# LCD.net
KiCad netlist of a schematic drawn in Altium Designer
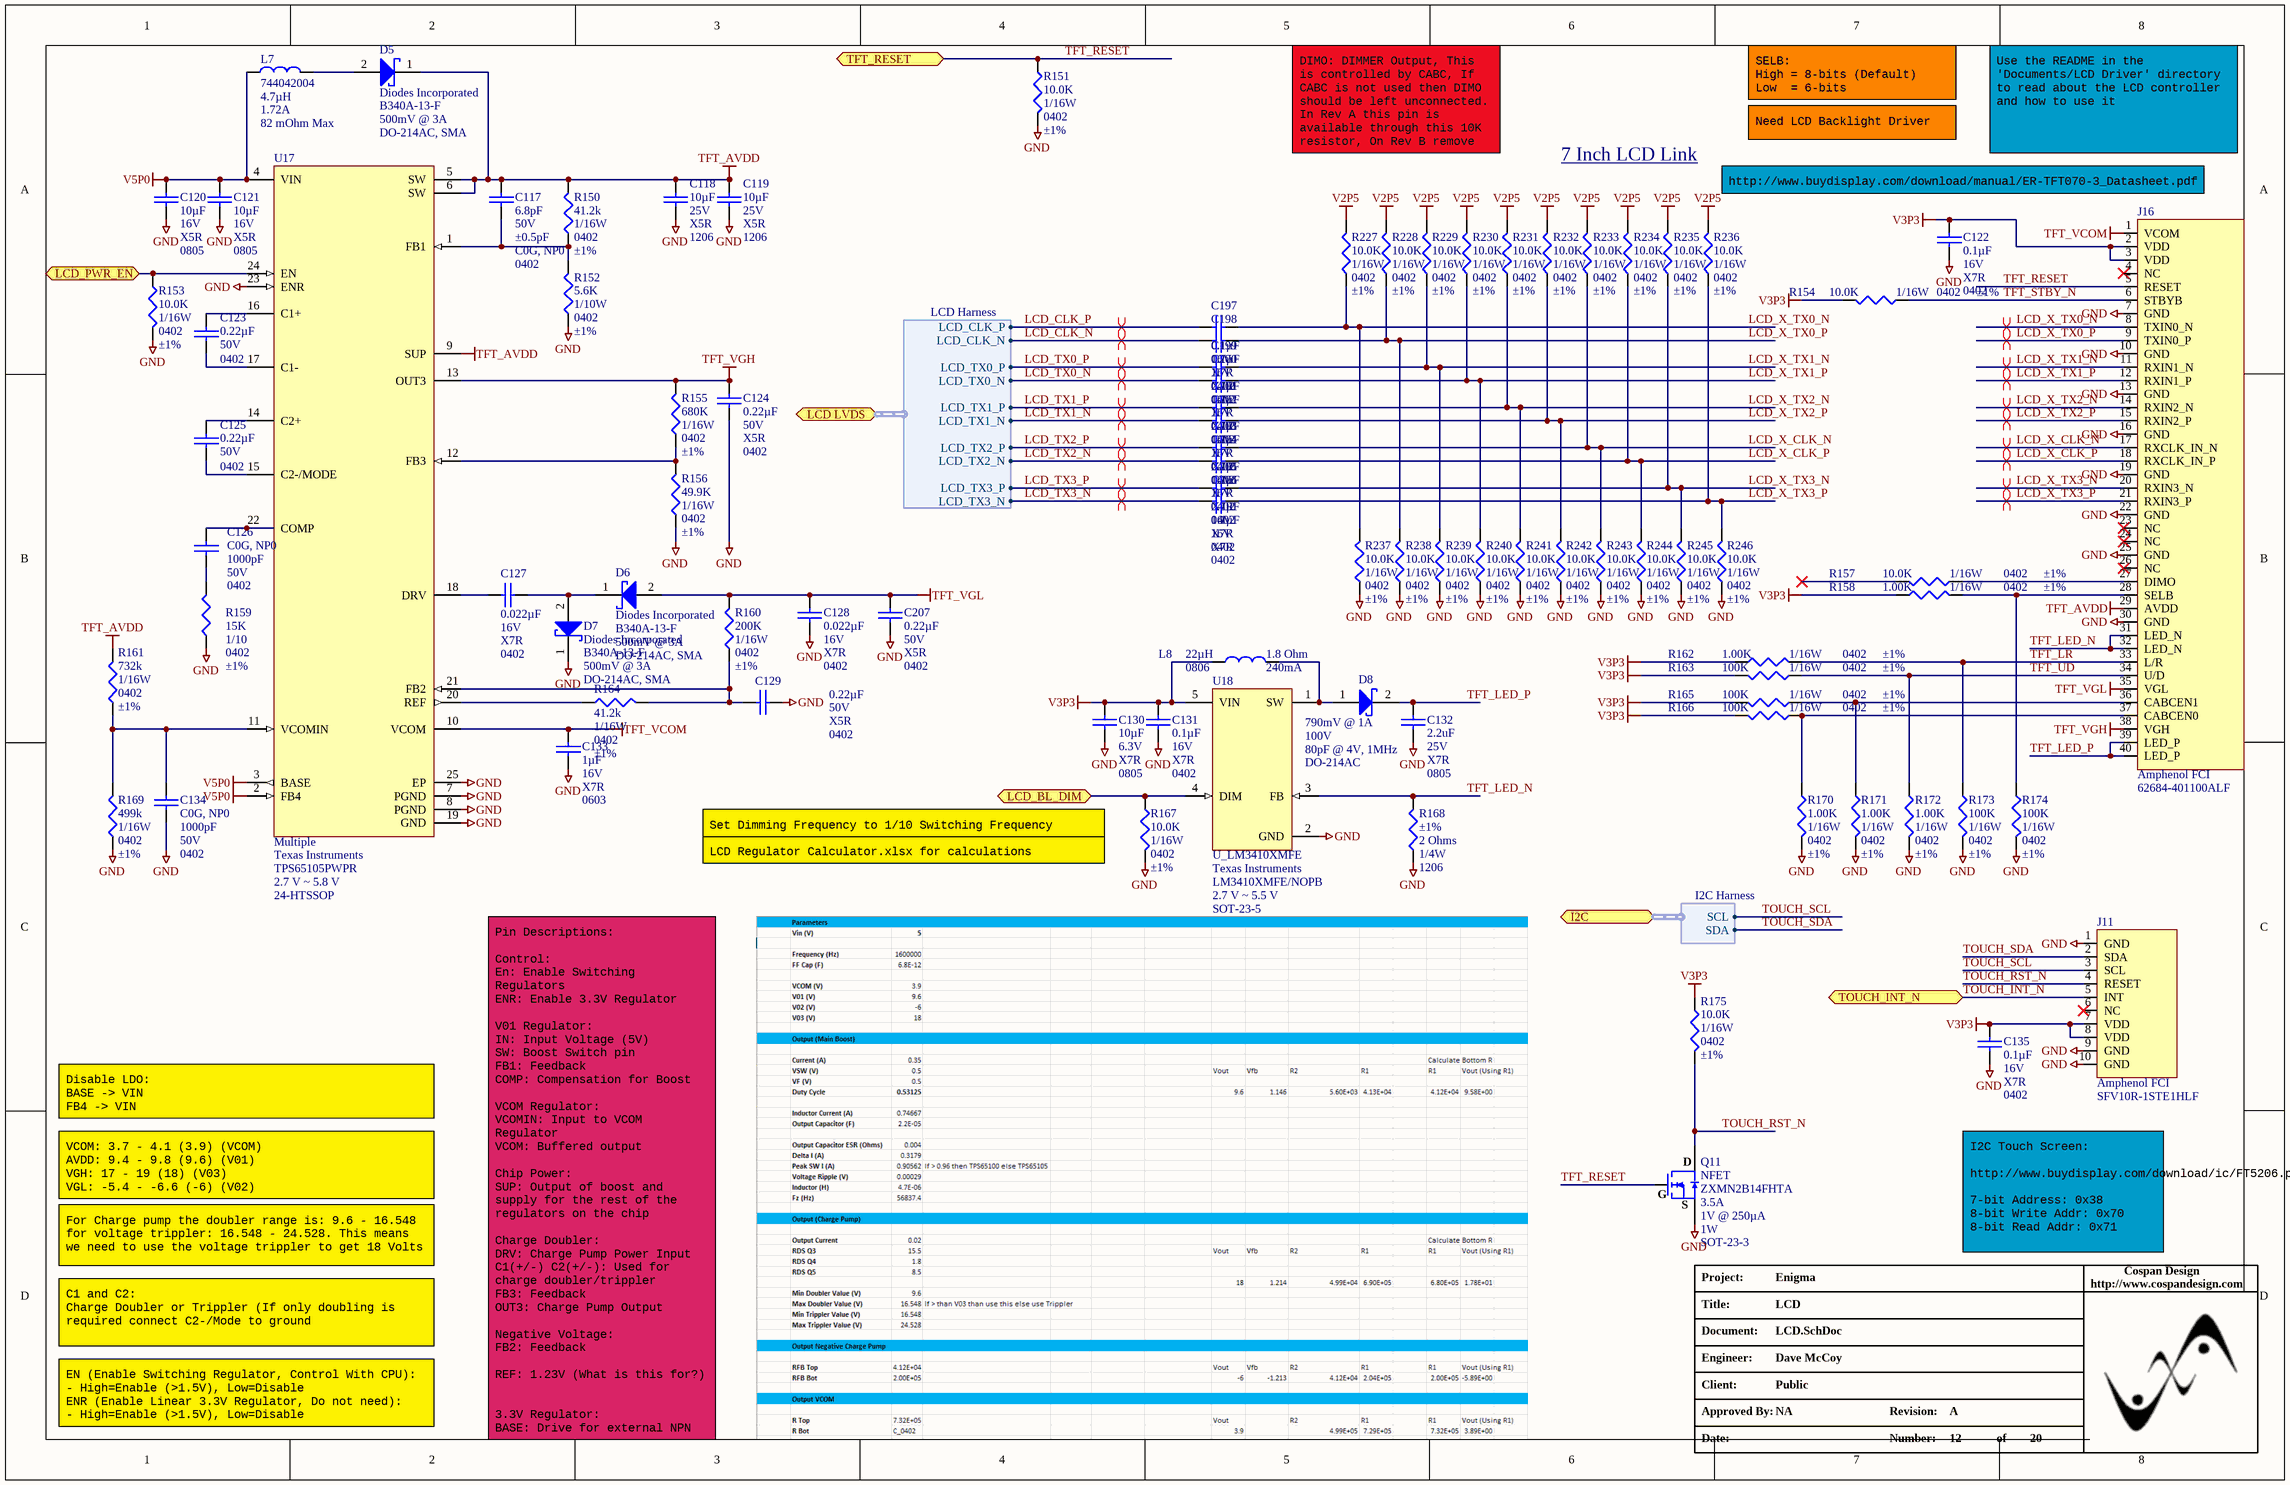
[diagram p0: LCD.SchDoc]

(export (version "E")
  (design (tool "Eeschema 10.0.6"))
  (components
    (comp (ref "C117")
      (value "6.8pF")
      (footprint "C_ERA-0402")
      (description "CAP CER 6.8PF 50V NP0 0402")
      (fields
        (field (name "MANUFACTURER") "Yageo")
        (field (name "MANUFACTURER PART NUMBER") "CC0402DRNPO9BN6R8")
        (field (name "CAPACITANCE") "6.8pF")
        (field (name "VOLTAGE - RATED") "50V")
        (field (name "TOLERANCE") "±0.5pF")
        (field (name "TEMPERATURE COEFFICIENT") "C0G, NP0")
        (field (name "PACKAGE / CASE") "0402")
      )
      (libsource (lib "Main LibraryX") (part "C_0402_6.8PF_50V"))
    )
    (comp (ref "C118")
      (value "10µF")
      (footprint "CAP-1206")
      (description "CAP CER 10UF 25V X5R 1206")
      (fields
        (field (name "MANUFACTURER") "Murata Electronics North America")
        (field (name "MANUFACTURER PART NUMBER") "GRM31CR61E106MA12L")
        (field (name "CAPACITANCE") "10µF")
        (field (name "VOLTAGE - RATED") "25V")
        (field (name "TEMPERATURE COEFFICIENT") "X5R")
        (field (name "PACKAGE / CASE") "1206")
      )
      (libsource (lib "Main Library") (part "C_1206_10UF_25V"))
    )
    (comp (ref "C119")
      (value "10µF")
      (footprint "CAP-1206")
      (description "CAP CER 10UF 25V X5R 1206")
      (fields
        (field (name "MANUFACTURER") "Murata Electronics North America")
        (field (name "MANUFACTURER PART NUMBER") "GRM31CR61E106MA12L")
        (field (name "CAPACITANCE") "10µF")
        (field (name "VOLTAGE - RATED") "25V")
        (field (name "TEMPERATURE COEFFICIENT") "X5R")
        (field (name "PACKAGE / CASE") "1206")
      )
      (libsource (lib "Main Library") (part "C_1206_10UF_25V"))
    )
    (comp (ref "C120")
      (value "10µF")
      (footprint "C_ERA-0805")
      (description "CAP CER 10uF 16V X5R 20% 0805")
      (fields
        (field (name "MANUFACTURER") "Taiyo Yuden")
        (field (name "MANUFACTURER PART NUMBER") "EMK212BJ106KG-T")
        (field (name "CAPACITANCE") "10µF")
        (field (name "VOLTAGE - RATED") "16V")
        (field (name "TEMPERATURE COEFFICIENT") "X5R")
        (field (name "PACKAGE / CASE") "0805")
      )
      (libsource (lib "Main LibraryX") (part "C_0805_10UF_16V"))
    )
    (comp (ref "C121")
      (value "10µF")
      (footprint "C_ERA-0805")
      (description "CAP CER 10uF 16V X5R 20% 0805")
      (fields
        (field (name "MANUFACTURER") "Taiyo Yuden")
        (field (name "MANUFACTURER PART NUMBER") "EMK212BJ106KG-T")
        (field (name "CAPACITANCE") "10µF")
        (field (name "VOLTAGE - RATED") "16V")
        (field (name "TEMPERATURE COEFFICIENT") "X5R")
        (field (name "PACKAGE / CASE") "0805")
      )
      (libsource (lib "Main LibraryX") (part "C_0805_10UF_16V"))
    )
    (comp (ref "C122")
      (value "0.1uF")
      (footprint "C_0402")
      (description "CAP CER .10UF 16V X7R 0402")
      (fields
        (field (name "MANUFACTURER") "Murata Electronics North America")
        (field (name "MANUFACTURER PART NUMBER") "GRM155R71C104KA88J")
        (field (name "CAPACITANCE") "0.1µF")
        (field (name "VOLTAGE - RATED") "16V")
        (field (name "TEMPERATURE COEFFICIENT") "X7R")
        (field (name "PACKAGE / CASE") "0402")
      )
      (libsource (lib "Main LibraryX") (part "C_0402_0.1UF_16V"))
    )
    (comp (ref "C123")
      (value "C_0402_0.22UF_50V")
      (footprint "C_ERA-0402")
      (description "CAP CER 0.22UF 50V X5R 0402")
      (fields
        (field (name "MANUFACTURER") "Taiyo Yuden")
        (field (name "MANUFACTURER PART NUMBER") "UMK105BJ224KV-F")
        (field (name "CAPACITANCE") "0.22µF")
        (field (name "VOLTAGE - RATED") "50V")
        (field (name "PACKAGE / CASE") "0402")
      )
      (libsource (lib "Main Library") (part "C_0402_0.22UF_50V"))
    )
    (comp (ref "C124")
      (value "C_0402_0.22UF_50V")
      (footprint "C_ERA-0402")
      (description "CAP CER 0.22UF 50V X5R 0402")
      (fields
        (field (name "MANUFACTURER") "Taiyo Yuden")
        (field (name "MANUFACTURER PART NUMBER") "UMK105BJ224KV-F")
        (field (name "CAPACITANCE") "0.22µF")
        (field (name "VOLTAGE - RATED") "50V")
        (field (name "TEMPERATURE COEFFICIENT") "X5R")
        (field (name "PACKAGE / CASE") "0402")
      )
      (libsource (lib "Main Library") (part "C_0402_0.22UF_50V"))
    )
    (comp (ref "C125")
      (value "C_0402_0.22UF_50V")
      (footprint "C_ERA-0402")
      (description "CAP CER 0.22UF 50V X5R 0402")
      (fields
        (field (name "MANUFACTURER") "Taiyo Yuden")
        (field (name "MANUFACTURER PART NUMBER") "UMK105BJ224KV-F")
        (field (name "CAPACITANCE") "0.22µF")
        (field (name "VOLTAGE - RATED") "50V")
        (field (name "PACKAGE / CASE") "0402")
      )
      (libsource (lib "Main Library") (part "C_0402_0.22UF_50V"))
    )
    (comp (ref "C126")
      (value "1000pF")
      (footprint "C_ERA-0402")
      (description "CAP CER 1000PF 50V C0G 0402")
      (fields
        (field (name "MANUFACTURER") "Murata Electronics North America")
        (field (name "MANUFACTURER PART NUMBER") "GRM1555C1H102JA01D")
        (field (name "TEMPERATURE COEFFICIENT") "C0G, NP0")
        (field (name "CAPACITANCE") "1000pF")
        (field (name "VOLTAGE - RATED") "50V")
        (field (name "PACKAGE / CASE") "0402")
      )
      (libsource (lib "Main Library") (part "C_0402_1000PF_50V"))
    )
    (comp (ref "C127")
      (value "0.022UF")
      (footprint "C_ERA-0402")
      (description "CAP CER 22000PF 16V X7R 0402")
      (fields
        (field (name "MANUFACTURER") "Murata Electronics North America")
        (field (name "MANUFACTURER PART NUMBER") "GRM155R71C223KA01D")
        (field (name "CAPACITANCE") "0.022µF")
        (field (name "VOLTAGE - RATED") "16V")
        (field (name "TEMPERATURE COEFFICIENT") "X7R")
        (field (name "PACKAGE / CASE") "0402")
      )
      (libsource (lib "Main Library") (part "C_0402_0.022UF"))
    )
    (comp (ref "C128")
      (value "0.022UF")
      (footprint "C_ERA-0402")
      (description "CAP CER 22000PF 16V X7R 0402")
      (fields
        (field (name "MANUFACTURER") "Murata Electronics North America")
        (field (name "MANUFACTURER PART NUMBER") "GRM155R71C223KA01D")
        (field (name "CAPACITANCE") "0.022µF")
        (field (name "VOLTAGE - RATED") "16V")
        (field (name "TEMPERATURE COEFFICIENT") "X7R")
        (field (name "PACKAGE / CASE") "0402")
      )
      (libsource (lib "Main Library") (part "C_0402_0.022UF"))
    )
    (comp (ref "C129")
      (value "C_0402_0.22UF_50V")
      (footprint "C_ERA-0402")
      (description "CAP CER 0.22UF 50V X5R 0402")
      (fields
        (field (name "MANUFACTURER") "Taiyo Yuden")
        (field (name "MANUFACTURER PART NUMBER") "UMK105BJ224KV-F")
        (field (name "CAPACITANCE") "0.22µF")
        (field (name "VOLTAGE - RATED") "50V")
        (field (name "TEMPERATURE COEFFICIENT") "X5R")
        (field (name "PACKAGE / CASE") "0402")
      )
      (libsource (lib "Main Library") (part "C_0402_0.22UF_50V"))
    )
    (comp (ref "C130")
      (value "10uF")
      (footprint "C_ERA-0805")
      (description "CAP CER 10UF 6.3V X7R 10% 0805")
      (fields
        (field (name "MANUFACTURER") "Taiyo Yuden")
        (field (name "MANUFACTURER PART NUMBER") "JMK212BJ106KD-T")
        (field (name "CAPACITANCE") "10µF")
        (field (name "VOLTAGE - RATED") "6.3V")
        (field (name "TEMPERATURE COEFFICIENT") "X7R")
        (field (name "PACKAGE / CASE") "0805")
      )
      (libsource (lib "Main LibraryX") (part "C_0805_10UF_6.3V"))
    )
    (comp (ref "C131")
      (value "0.1uF")
      (footprint "C_0402")
      (description "CAP CER .10UF 16V X7R 0402")
      (fields
        (field (name "MANUFACTURER") "Murata Electronics North America")
        (field (name "MANUFACTURER PART NUMBER") "GRM155R71C104KA88J")
        (field (name "CAPACITANCE") "0.1µF")
        (field (name "VOLTAGE - RATED") "16V")
        (field (name "TEMPERATURE COEFFICIENT") "X7R")
        (field (name "PACKAGE / CASE") "0402")
      )
      (libsource (lib "Main LibraryX") (part "C_0402_0.1UF_16V"))
    )
    (comp (ref "C132")
      (value "C_0805_2.2uF_25V")
      (footprint "C_ERA-0805")
      (fields
        (field (name "MANUFACTURER") "Taiyo Yuden")
        (field (name "MANUFACTURER PART NUMBER") "TMK212B7225KG-TR")
        (field (name "TOLERANCE") "±10%")
        (field (name "CAPACITANCE") "2.2uF")
        (field (name "VOLTAGE - RATED") "25V")
        (field (name "TEMPERATURE COEFFICIENT") "X7R")
        (field (name "PACKAGE / CASE") "0805")
      )
      (libsource (lib "Cospan Design") (part "C_0805_2.2uF_25V"))
    )
    (comp (ref "C133")
      (value "C_0603_1µF_16V")
      (footprint "C_ERA-0603")
      (description "CAP CER 1UF 16V X7R 0603")
      (fields
        (field (name "MANUFACTURER") "Yageo")
        (field (name "MANUFACTURER PART NUMBER") "CC0603KRX7R7BB105")
        (field (name "CAPACITANCE") "1µF")
        (field (name "VOLTAGE - RATED") "16V")
        (field (name "TEMPERATURE COEFFICIENT") "X7R")
        (field (name "PACKAGE / CASE") "0603")
      )
      (libsource (lib "Cospan Design") (part "C_0603_1µF_16V"))
    )
    (comp (ref "C134")
      (value "1000pF")
      (footprint "C_ERA-0402")
      (description "CAP CER 1000PF 50V C0G 0402")
      (fields
        (field (name "MANUFACTURER") "Murata Electronics North America")
        (field (name "MANUFACTURER PART NUMBER") "GRM1555C1H102JA01D")
        (field (name "TEMPERATURE COEFFICIENT") "C0G, NP0")
        (field (name "CAPACITANCE") "1000pF")
        (field (name "VOLTAGE - RATED") "50V")
        (field (name "PACKAGE / CASE") "0402")
      )
      (libsource (lib "Main Library") (part "C_0402_1000PF_50V"))
    )
    (comp (ref "C135")
      (value "0.1uF")
      (footprint "C_0402")
      (description "CAP CER .10UF 16V X7R 0402")
      (fields
        (field (name "MANUFACTURER") "Murata Electronics North America")
        (field (name "MANUFACTURER PART NUMBER") "GRM155R71C104KA88J")
        (field (name "CAPACITANCE") "0.1µF")
        (field (name "VOLTAGE - RATED") "16V")
        (field (name "TEMPERATURE COEFFICIENT") "X7R")
        (field (name "PACKAGE / CASE") "0402")
      )
      (libsource (lib "Main LibraryX") (part "C_0402_0.1UF_16V"))
    )
    (comp (ref "C197")
      (value "0.1uF")
      (footprint "C_0402")
      (description "CAP CER .10UF 16V X7R 0402")
      (fields
        (field (name "MANUFACTURER") "Murata Electronics North America")
        (field (name "MANUFACTURER PART NUMBER") "GRM155R71C104KA88J")
        (field (name "CAPACITANCE") "0.1µF")
        (field (name "VOLTAGE - RATED") "16V")
        (field (name "TEMPERATURE COEFFICIENT") "X7R")
        (field (name "PACKAGE / CASE") "0402")
      )
      (libsource (lib "Main LibraryX") (part "C_0402_0.1UF_16V"))
    )
    (comp (ref "C198")
      (value "0.1uF")
      (footprint "C_0402")
      (description "CAP CER .10UF 16V X7R 0402")
      (fields
        (field (name "MANUFACTURER") "Murata Electronics North America")
        (field (name "MANUFACTURER PART NUMBER") "GRM155R71C104KA88J")
        (field (name "CAPACITANCE") "0.1µF")
        (field (name "VOLTAGE - RATED") "16V")
        (field (name "TEMPERATURE COEFFICIENT") "X7R")
        (field (name "PACKAGE / CASE") "0402")
      )
      (libsource (lib "Main LibraryX") (part "C_0402_0.1UF_16V"))
    )
    (comp (ref "C199")
      (value "0.1uF")
      (footprint "C_0402")
      (description "CAP CER .10UF 16V X7R 0402")
      (fields
        (field (name "MANUFACTURER") "Murata Electronics North America")
        (field (name "MANUFACTURER PART NUMBER") "GRM155R71C104KA88J")
        (field (name "CAPACITANCE") "0.1µF")
        (field (name "VOLTAGE - RATED") "16V")
        (field (name "TEMPERATURE COEFFICIENT") "X7R")
        (field (name "PACKAGE / CASE") "0402")
      )
      (libsource (lib "Main LibraryX") (part "C_0402_0.1UF_16V"))
    )
    (comp (ref "C200")
      (value "0.1uF")
      (footprint "C_0402")
      (description "CAP CER .10UF 16V X7R 0402")
      (fields
        (field (name "MANUFACTURER") "Murata Electronics North America")
        (field (name "MANUFACTURER PART NUMBER") "GRM155R71C104KA88J")
        (field (name "CAPACITANCE") "0.1µF")
        (field (name "VOLTAGE - RATED") "16V")
        (field (name "TEMPERATURE COEFFICIENT") "X7R")
        (field (name "PACKAGE / CASE") "0402")
      )
      (libsource (lib "Main LibraryX") (part "C_0402_0.1UF_16V"))
    )
    (comp (ref "C201")
      (value "0.1uF")
      (footprint "C_0402")
      (description "CAP CER .10UF 16V X7R 0402")
      (fields
        (field (name "MANUFACTURER") "Murata Electronics North America")
        (field (name "MANUFACTURER PART NUMBER") "GRM155R71C104KA88J")
        (field (name "CAPACITANCE") "0.1µF")
        (field (name "VOLTAGE - RATED") "16V")
        (field (name "TEMPERATURE COEFFICIENT") "X7R")
        (field (name "PACKAGE / CASE") "0402")
      )
      (libsource (lib "Main LibraryX") (part "C_0402_0.1UF_16V"))
    )
    (comp (ref "C202")
      (value "0.1uF")
      (footprint "C_0402")
      (description "CAP CER .10UF 16V X7R 0402")
      (fields
        (field (name "MANUFACTURER") "Murata Electronics North America")
        (field (name "MANUFACTURER PART NUMBER") "GRM155R71C104KA88J")
        (field (name "CAPACITANCE") "0.1µF")
        (field (name "VOLTAGE - RATED") "16V")
        (field (name "TEMPERATURE COEFFICIENT") "X7R")
        (field (name "PACKAGE / CASE") "0402")
      )
      (libsource (lib "Main LibraryX") (part "C_0402_0.1UF_16V"))
    )
    (comp (ref "C203")
      (value "0.1uF")
      (footprint "C_0402")
      (description "CAP CER .10UF 16V X7R 0402")
      (fields
        (field (name "MANUFACTURER") "Murata Electronics North America")
        (field (name "MANUFACTURER PART NUMBER") "GRM155R71C104KA88J")
        (field (name "CAPACITANCE") "0.1µF")
        (field (name "VOLTAGE - RATED") "16V")
        (field (name "TEMPERATURE COEFFICIENT") "X7R")
        (field (name "PACKAGE / CASE") "0402")
      )
      (libsource (lib "Main LibraryX") (part "C_0402_0.1UF_16V"))
    )
    (comp (ref "C204")
      (value "0.1uF")
      (footprint "C_0402")
      (description "CAP CER .10UF 16V X7R 0402")
      (fields
        (field (name "MANUFACTURER") "Murata Electronics North America")
        (field (name "MANUFACTURER PART NUMBER") "GRM155R71C104KA88J")
        (field (name "CAPACITANCE") "0.1µF")
        (field (name "VOLTAGE - RATED") "16V")
        (field (name "TEMPERATURE COEFFICIENT") "X7R")
        (field (name "PACKAGE / CASE") "0402")
      )
      (libsource (lib "Main LibraryX") (part "C_0402_0.1UF_16V"))
    )
    (comp (ref "C205")
      (value "0.1uF")
      (footprint "C_0402")
      (description "CAP CER .10UF 16V X7R 0402")
      (fields
        (field (name "MANUFACTURER") "Murata Electronics North America")
        (field (name "MANUFACTURER PART NUMBER") "GRM155R71C104KA88J")
        (field (name "CAPACITANCE") "0.1µF")
        (field (name "VOLTAGE - RATED") "16V")
        (field (name "TEMPERATURE COEFFICIENT") "X7R")
        (field (name "PACKAGE / CASE") "0402")
      )
      (libsource (lib "Main LibraryX") (part "C_0402_0.1UF_16V"))
    )
    (comp (ref "C206")
      (value "0.1uF")
      (footprint "C_0402")
      (description "CAP CER .10UF 16V X7R 0402")
      (fields
        (field (name "MANUFACTURER") "Murata Electronics North America")
        (field (name "MANUFACTURER PART NUMBER") "GRM155R71C104KA88J")
        (field (name "CAPACITANCE") "0.1µF")
        (field (name "VOLTAGE - RATED") "16V")
        (field (name "TEMPERATURE COEFFICIENT") "X7R")
        (field (name "PACKAGE / CASE") "0402")
      )
      (libsource (lib "Main LibraryX") (part "C_0402_0.1UF_16V"))
    )
    (comp (ref "C207")
      (value "C_0402_0.22UF_50V")
      (footprint "C_ERA-0402")
      (description "CAP CER 0.22UF 50V X5R 0402")
      (fields
        (field (name "MANUFACTURER") "Taiyo Yuden")
        (field (name "MANUFACTURER PART NUMBER") "UMK105BJ224KV-F")
        (field (name "CAPACITANCE") "0.22µF")
        (field (name "VOLTAGE - RATED") "50V")
        (field (name "TEMPERATURE COEFFICIENT") "X5R")
        (field (name "PACKAGE / CASE") "0402")
      )
      (libsource (lib "Main Library") (part "C_0402_0.22UF_50V"))
    )
    (comp (ref "D5")
      (value "D_B340A-13-F")
      (footprint "SMA")
      (description "DIODE SCHOTTKY 40V 3A SMA")
      (fields
        (field (name "MANUFACTURER") "Diodes Incorporated")
        (field (name "MANUFACTURER PART NUMBER") "B340A-13-F")
        (field (name "VOLTAGE - FORWARD (VF) (MAX) @ IF") "500mV @ 3A")
        (field (name "PACKAGE / CASE") "DO-214AC, SMA")
      )
      (libsource (lib "Cospan Design") (part "D_B340A-13-F"))
    )
    (comp (ref "D6")
      (value "D_B340A-13-F")
      (footprint "SMA")
      (description "DIODE SCHOTTKY 40V 3A SMA")
      (fields
        (field (name "MANUFACTURER") "Diodes Incorporated")
        (field (name "MANUFACTURER PART NUMBER") "B340A-13-F")
        (field (name "VOLTAGE - FORWARD (VF) (MAX) @ IF") "500mV @ 3A")
        (field (name "PACKAGE / CASE") "DO-214AC, SMA")
      )
      (libsource (lib "Cospan Design") (part "D_B340A-13-F"))
    )
    (comp (ref "D7")
      (value "D_B340A-13-F")
      (footprint "SMA")
      (description "DIODE SCHOTTKY 40V 3A SMA")
      (fields
        (field (name "MANUFACTURER") "Diodes Incorporated")
        (field (name "MANUFACTURER PART NUMBER") "B340A-13-F")
        (field (name "VOLTAGE - FORWARD (VF) (MAX) @ IF") "500mV @ 3A")
        (field (name "PACKAGE / CASE") "DO-214AC, SMA")
      )
      (libsource (lib "Cospan Design") (part "D_B340A-13-F"))
    )
    (comp (ref "D8")
      (value "B1100-13-F")
      (footprint "DIOM5226X23L")
      (description "DIODE SCHOTTKY 100V 1A SMA")
      (fields
        (field (name "MANUFACTURER") "Diodes Inc")
        (field (name "VOLTAGE - FORWARD (VF) (MAX) @ IF") "790mV @ 1A")
        (field (name "VOLTAGE - DC REVERSE (VR) (MAX)") "100V")
        (field (name "CAPACITANCE @ VR, F") "80pF @ 4V, 1MHz")
        (field (name "PACKAGE / CASE") "DO-214AC")
      )
      (libsource (lib "Main Library") (part "D_SCHOTT_B1100-13-F"))
    )
    (comp (ref "J11")
      (value "J_FFC_CONN_RA_10PIN")
      (footprint "ER-CON10HT-1_BTM")
      (description "CONN FFC BOTTOM 10POS 0.50MM R/A")
      (fields
        (field (name "MANUFACTURER") "Amphenol FCI")
        (field (name "MANUFACTURER PART NUMBER") "SFV10R-1STE1HLF")
      )
      (libsource (lib "Cospan Design") (part "J_FFC_CONN_RA_10PIN"))
    )
    (comp (ref "J16")
      (value "J_FFC_CONN_RA_40PIN")
      (footprint "ER-CON40HT-1_BTM")
      (description "CONN FPC BOTTOM 40POS 0.50MM R/A")
      (fields
        (field (name "MANUFACTURER") "Amphenol FCI")
        (field (name "MANUFACTURER PART NUMBER") "62684-401100ALF")
      )
      (libsource (lib "Cospan Design") (part "J_FFC_CONN_RA_40PIN"))
    )
    (comp (ref "L7")
      (value "4.7uH")
      (footprint "INDP744042006")
      (description "INDUCTOR POWER 4.7UH 1.72A SMD")
      (fields
        (field (name "MANUFACTURER") "Wurth Electronics Inc")
        (field (name "TOLERANCE") "±30%")
        (field (name "MANUFACTURER PART NUMBER") "744042004")
        (field (name "INDUCTANCE") "4.7µH")
        (field (name "CURRENT") "1.72A")
        (field (name "DC RESISTANCE (DCR)") "82 mOhm Max")
      )
      (libsource (lib "Main Library") (part "L_4.70UH_1.72A_SMD"))
    )
    (comp (ref "L8")
      (value "CBC2016T220K")
      (footprint "L_0806")
      (description "INDUCTOR 22UH 10% 0806 SMD")
      (fields
        (field (name "MANUFACTURER") "Taiyo Yuden")
        (field (name "TOLERANCE") "±10%")
        (field (name "CURRENT") "240mA")
        (field (name "PACKAGE / CASE") "0806")
        (field (name "INDUCTANCE") "22µH")
        (field (name "DC RESISTANCE (DCR)") "1.8 Ohm")
      )
      (libsource (lib "Main Library") (part "L_0806_22uH"))
    )
    (comp (ref "Q11")
      (value "NFET")
      (footprint "SOT-23A")
      (description "MOSFET N-CH 20V 3.5A SOT23-3")
      (fields
        (field (name "MANUFACTURER") "Diodes Incorporated")
        (field (name "MANUFACTURER PART NUMBER") "ZXMN2B14FHTA")
        (field (name "CURRENT - CONTINUOUS DRAIN (ID) @ 25° C") "3.5A")
        (field (name "VGS(TH) (MAX) @ ID") "1V @ 250µA")
        (field (name "POWER - MAX") "1W")
        (field (name "PACKAGE / CASE") "SOT-23-3")
      )
      (libsource (lib "Main Library") (part "Q_NFET_3.50A_SOT23"))
    )
    (comp (ref "R150")
      (value "R_0402_41.2K")
      (footprint "R_0402")
      (description "RES SMD 41.2K OHM 1% 1/16W 0402")
      (fields
        (field (name "RESISTANCE IN OHMS") "41.2k")
        (field (name "POWER (WATTS)") "1/16W")
        (field (name "CASE") "0402")
        (field (name "TOLERANCE") "±1%")
        (field (name "MANUFACTURER") "Yageo")
        (field (name "MANUFACTURER PART NUMBER") "RC0402FR-0741K2L")
      )
      (libsource (lib "Cospan Design") (part "R_0402_41.2K"))
    )
    (comp (ref "R151")
      (value "R_0402_10.0K")
      (footprint "R_0402")
      (description "RES 10.0K OHM 1/16W 1% 0402 SMD")
      (fields
        (field (name "MANUFACTURER") "Stackpole Electronics Inc")
        (field (name "MANUFACTURER PART NUMBER") "RMCF0402FT10K0")
        (field (name "RESISTANCE IN OHMS") "10.0K")
        (field (name "POWER (WATTS)") "1/16W")
        (field (name "CASE") "0402")
        (field (name "TOLERANCE") "±1%")
      )
      (libsource (lib "Cospan Design") (part "R_0402_10.0K"))
    )
    (comp (ref "R152")
      (value "5.6k Ohms")
      (footprint "R_0402")
      (description "RES 5.60K OHM 1/10W 1% 0402 SMD")
      (fields
        (field (name "MANUFACTURER") "Yageo")
        (field (name "MANUFACTURER PART NUMBER") "RC0402FR-075K6L")
        (field (name "RESISTANCE IN OHMS") "5.6K")
        (field (name "POWER (WATTS)") "1/10W")
        (field (name "CASE") "0402")
        (field (name "TOLERANCE") "±1%")
      )
      (libsource (lib "Main LibraryX") (part "R_0402_5.6K"))
    )
    (comp (ref "R153")
      (value "R_0402_10.0K")
      (footprint "R_0402")
      (description "RES 10.0K OHM 1/16W 1% 0402 SMD")
      (fields
        (field (name "MANUFACTURER") "Stackpole Electronics Inc")
        (field (name "MANUFACTURER PART NUMBER") "RMCF0402FT10K0")
        (field (name "RESISTANCE IN OHMS") "10.0K")
        (field (name "POWER (WATTS)") "1/16W")
        (field (name "CASE") "0402")
        (field (name "TOLERANCE") "±1%")
      )
      (libsource (lib "Cospan Design") (part "R_0402_10.0K"))
    )
    (comp (ref "R154")
      (value "R_0402_10.0K")
      (footprint "R_0402")
      (description "RES 10.0K OHM 1/16W 1% 0402 SMD")
      (fields
        (field (name "MANUFACTURER") "Stackpole Electronics Inc")
        (field (name "MANUFACTURER PART NUMBER") "RMCF0402FT10K0")
        (field (name "RESISTANCE IN OHMS") "10.0K")
        (field (name "POWER (WATTS)") "1/16W")
        (field (name "CASE") "0402")
        (field (name "TOLERANCE") "±1%")
      )
      (libsource (lib "Cospan Design") (part "R_0402_10.0K"))
    )
    (comp (ref "R155")
      (value "R_0402_680K")
      (footprint "R_0402")
      (description "Res Thick Film 0402 68K Ohm 1% 0.1W(1/10W) Â±100ppm/Â°C Molded SMD Automotive Punched T/R")
      (fields
        (field (name "MANUFACTURER") "Yageo")
        (field (name "MANUFACTURER PART NUMBER") "RC0402FR-07680KL")
        (field (name "RESISTANCE IN OHMS") "680K")
        (field (name "POWER (WATTS)") "1/16W")
        (field (name "CASE") "0402")
        (field (name "TOLERANCE") "±1%")
      )
      (libsource (lib "Cospan Design") (part "R_0402_680K"))
    )
    (comp (ref "R156")
      (value "R_0402_49.9K")
      (footprint "R_0402")
      (description "RES 49.9K OHM 1/16W 1% 0402 SMD")
      (fields
        (field (name "MANUFACTURER") "Vishay Dale")
        (field (name "MANUFACTURER PART NUMBER") "CRCW040249K9FKED")
        (field (name "RESISTANCE IN OHMS") "49.9K")
        (field (name "POWER (WATTS)") "1/16W")
        (field (name "CASE") "0402")
        (field (name "TOLERANCE") "±1%")
      )
      (libsource (lib "Main LibraryX") (part "R_0402_49.9K"))
    )
    (comp (ref "R157")
      (value "R_0402_10.0K")
      (footprint "R_0402")
      (description "RES 10.0K OHM 1/16W 1% 0402 SMD")
      (fields
        (field (name "MANUFACTURER") "Stackpole Electronics Inc")
        (field (name "MANUFACTURER PART NUMBER") "RMCF0402FT10K0")
        (field (name "RESISTANCE IN OHMS") "10.0K")
        (field (name "POWER (WATTS)") "1/16W")
        (field (name "CASE") "0402")
        (field (name "TOLERANCE") "±1%")
      )
      (libsource (lib "Cospan Design") (part "R_0402_10.0K"))
    )
    (comp (ref "R158")
      (value "1.0k Ohms")
      (footprint "R_0402")
      (description "RES 1.00K OHM 1/16W 1% 0402 SMD")
      (fields
        (field (name "MANUFACTURER") "Yageo")
        (field (name "MANUFACTURER PART NUMBER") "RC0402FR-071KL")
        (field (name "RESISTANCE IN OHMS") "1.00K")
        (field (name "POWER (WATTS)") "1/16W")
        (field (name "CASE") "0402")
        (field (name "TOLERANCE") "±1%")
      )
      (libsource (lib "Cospan Design") (part "R_0402_1.0K"))
    )
    (comp (ref "R159")
      (value "R_0402_15.0K")
      (footprint "R_0402")
      (description "RES 15.0K OHM 1/10W 1% 0402 SMD")
      (fields
        (field (name "MANUFACTURER") "Panasonic - ECG")
        (field (name "MANUFACTURER PART NUMBER") "ERJ-2RKF1502X")
        (field (name "RESISTANCE IN OHMS") "15K")
        (field (name "POWER (WATTS)") "1/10")
        (field (name "CASE") "0402")
        (field (name "TOLERANCE") "±1%")
      )
      (libsource (lib "Main Library") (part "R_0402_15.0K"))
    )
    (comp (ref "R160")
      (value "R_0402_200.0K")
      (footprint "R_0402")
      (description "RES 200K OHM 1/16W 1% 0402 SMD")
      (fields
        (field (name "MANUFACTURER") "Yageo")
        (field (name "MANUFACTURER PART NUMBER") "RC0402FR-07200KL")
        (field (name "RESISTANCE IN OHMS") "200K")
        (field (name "POWER (WATTS)") "1/16W")
        (field (name "CASE") "0402")
        (field (name "TOLERANCE") "±1%")
      )
      (libsource (lib "Main Library") (part "R_0402_200.0K"))
    )
    (comp (ref "R161")
      (value "R_0402_732k")
      (footprint "R_0402")
      (description "RES SMD 732K OHM 1% 1/16W 0402")
      (fields
        (field (name "MANUFACTURER") "Yageo")
        (field (name "MANUFACTURER PART NUMBER") "RC0402FR-07732KL")
        (field (name "RESISTANCE IN OHMS") "732k")
        (field (name "POWER (WATTS)") "1/16W")
        (field (name "CASE") "0402")
        (field (name "TOLERANCE") "±1%")
      )
      (libsource (lib "Cospan Design") (part "R_0402_732k"))
    )
    (comp (ref "R162")
      (value "1.0k Ohms")
      (footprint "R_0402")
      (description "RES 1.00K OHM 1/16W 1% 0402 SMD")
      (fields
        (field (name "MANUFACTURER") "Yageo")
        (field (name "MANUFACTURER PART NUMBER") "RC0402FR-071KL")
        (field (name "RESISTANCE IN OHMS") "1.00K")
        (field (name "POWER (WATTS)") "1/16W")
        (field (name "CASE") "0402")
        (field (name "TOLERANCE") "±1%")
      )
      (libsource (lib "Cospan Design") (part "R_0402_1.0K"))
    )
    (comp (ref "R163")
      (value "R_0402_100K")
      (footprint "R_0402")
      (description "RES SMD 100K OHM 1% 1/16W 0402")
      (fields
        (field (name "MANUFACTURER") "Yageo")
        (field (name "MANUFACTURER PART NUMBER") "RC0402FR-07100KL")
        (field (name "RESISTANCE IN OHMS") "100K")
        (field (name "POWER (WATTS)") "1/16W")
        (field (name "CASE") "0402")
        (field (name "TOLERANCE") "±1%")
      )
      (libsource (lib "Cospan Design") (part "R_0402_100K"))
    )
    (comp (ref "R164")
      (value "R_0402_41.2K")
      (footprint "R_0402")
      (description "RES SMD 41.2K OHM 1% 1/16W 0402")
      (fields
        (field (name "RESISTANCE IN OHMS") "41.2k")
        (field (name "POWER (WATTS)") "1/16W")
        (field (name "CASE") "0402")
        (field (name "TOLERANCE") "±1%")
        (field (name "MANUFACTURER") "Yageo")
        (field (name "MANUFACTURER PART NUMBER") "RC0402FR-0741K2L")
      )
      (libsource (lib "Cospan Design") (part "R_0402_41.2K"))
    )
    (comp (ref "R165")
      (value "R_0402_100K")
      (footprint "R_0402")
      (description "RES SMD 100K OHM 1% 1/16W 0402")
      (fields
        (field (name "MANUFACTURER") "Yageo")
        (field (name "MANUFACTURER PART NUMBER") "RC0402FR-07100KL")
        (field (name "RESISTANCE IN OHMS") "100K")
        (field (name "POWER (WATTS)") "1/16W")
        (field (name "CASE") "0402")
        (field (name "TOLERANCE") "±1%")
      )
      (libsource (lib "Cospan Design") (part "R_0402_100K"))
    )
    (comp (ref "R166")
      (value "R_0402_100K")
      (footprint "R_0402")
      (description "RES SMD 100K OHM 1% 1/16W 0402")
      (fields
        (field (name "MANUFACTURER") "Yageo")
        (field (name "MANUFACTURER PART NUMBER") "RC0402FR-07100KL")
        (field (name "RESISTANCE IN OHMS") "100K")
        (field (name "POWER (WATTS)") "1/16W")
        (field (name "CASE") "0402")
        (field (name "TOLERANCE") "±1%")
      )
      (libsource (lib "Cospan Design") (part "R_0402_100K"))
    )
    (comp (ref "R167")
      (value "R_0402_10.0K")
      (footprint "R_0402")
      (description "RES 10.0K OHM 1/16W 1% 0402 SMD")
      (fields
        (field (name "MANUFACTURER") "Stackpole Electronics Inc")
        (field (name "MANUFACTURER PART NUMBER") "RMCF0402FT10K0")
        (field (name "RESISTANCE IN OHMS") "10.0K")
        (field (name "POWER (WATTS)") "1/16W")
        (field (name "CASE") "0402")
        (field (name "TOLERANCE") "±1%")
      )
      (libsource (lib "Cospan Design") (part "R_0402_10.0K"))
    )
    (comp (ref "R168")
      (value "R_1206_2")
      (footprint "R_1206")
      (description "RES SMD 2 OHM 1% 1/4W 1206")
      (fields
        (field (name "MANUFACTURER") "Yageo")
        (field (name "MANUFACTURER PART NUMBER") "RC1206FR-072RL")
        (field (name "TOLERANCE") "±1%")
        (field (name "RESISTANCE IN OHMS") "2 Ohms")
        (field (name "POWER (WATTS)") "1/4W")
        (field (name "CASE") "1206")
      )
      (libsource (lib "Cospan Design") (part "R_1206_2"))
    )
    (comp (ref "R169")
      (value "R_0402_499k")
      (footprint "R_0402")
      (description "RES SMD 499K OHM 1% 1/16W 0402")
      (fields
        (field (name "MANUFACTURER") "Yageo")
        (field (name "MANUFACTURER PART NUMBER") "RC0402FR-07499KL")
        (field (name "RESISTANCE IN OHMS") "499k")
        (field (name "POWER (WATTS)") "1/16W")
        (field (name "CASE") "0402")
        (field (name "TOLERANCE") "±1%")
      )
      (libsource (lib "Main Library") (part "R_0402_499k"))
    )
    (comp (ref "R170")
      (value "1.0k Ohms")
      (footprint "R_0402")
      (description "RES 1.00K OHM 1/16W 1% 0402 SMD")
      (fields
        (field (name "MANUFACTURER") "Yageo")
        (field (name "MANUFACTURER PART NUMBER") "RC0402FR-071KL")
        (field (name "RESISTANCE IN OHMS") "1.00K")
        (field (name "POWER (WATTS)") "1/16W")
        (field (name "CASE") "0402")
        (field (name "TOLERANCE") "±1%")
      )
      (libsource (lib "Cospan Design") (part "R_0402_1.0K"))
    )
    (comp (ref "R171")
      (value "1.0k Ohms")
      (footprint "R_0402")
      (description "RES 1.00K OHM 1/16W 1% 0402 SMD")
      (fields
        (field (name "MANUFACTURER") "Yageo")
        (field (name "MANUFACTURER PART NUMBER") "RC0402FR-071KL")
        (field (name "RESISTANCE IN OHMS") "1.00K")
        (field (name "POWER (WATTS)") "1/16W")
        (field (name "CASE") "0402")
        (field (name "TOLERANCE") "±1%")
      )
      (libsource (lib "Cospan Design") (part "R_0402_1.0K"))
    )
    (comp (ref "R172")
      (value "1.0k Ohms")
      (footprint "R_0402")
      (description "RES 1.00K OHM 1/16W 1% 0402 SMD")
      (fields
        (field (name "MANUFACTURER") "Yageo")
        (field (name "MANUFACTURER PART NUMBER") "RC0402FR-071KL")
        (field (name "RESISTANCE IN OHMS") "1.00K")
        (field (name "POWER (WATTS)") "1/16W")
        (field (name "CASE") "0402")
        (field (name "TOLERANCE") "±1%")
      )
      (libsource (lib "Cospan Design") (part "R_0402_1.0K"))
    )
    (comp (ref "R173")
      (value "R_0402_100K")
      (footprint "R_0402")
      (description "RES SMD 100K OHM 1% 1/16W 0402")
      (fields
        (field (name "MANUFACTURER") "Yageo")
        (field (name "MANUFACTURER PART NUMBER") "RC0402FR-07100KL")
        (field (name "RESISTANCE IN OHMS") "100K")
        (field (name "POWER (WATTS)") "1/16W")
        (field (name "CASE") "0402")
        (field (name "TOLERANCE") "±1%")
      )
      (libsource (lib "Cospan Design") (part "R_0402_100K"))
    )
    (comp (ref "R174")
      (value "R_0402_100K")
      (footprint "R_0402")
      (description "RES SMD 100K OHM 1% 1/16W 0402")
      (fields
        (field (name "MANUFACTURER") "Yageo")
        (field (name "MANUFACTURER PART NUMBER") "RC0402FR-07100KL")
        (field (name "RESISTANCE IN OHMS") "100K")
        (field (name "POWER (WATTS)") "1/16W")
        (field (name "CASE") "0402")
        (field (name "TOLERANCE") "±1%")
      )
      (libsource (lib "Cospan Design") (part "R_0402_100K"))
    )
    (comp (ref "R175")
      (value "R_0402_10.0K")
      (footprint "R_0402")
      (description "RES 10.0K OHM 1/16W 1% 0402 SMD")
      (fields
        (field (name "MANUFACTURER") "Stackpole Electronics Inc")
        (field (name "MANUFACTURER PART NUMBER") "RMCF0402FT10K0")
        (field (name "RESISTANCE IN OHMS") "10.0K")
        (field (name "POWER (WATTS)") "1/16W")
        (field (name "CASE") "0402")
        (field (name "TOLERANCE") "±1%")
      )
      (libsource (lib "Cospan Design") (part "R_0402_10.0K"))
    )
    (comp (ref "R227")
      (value "R_0402_10.0K")
      (footprint "R_0402")
      (description "RES 10.0K OHM 1/16W 1% 0402 SMD")
      (fields
        (field (name "MANUFACTURER") "Stackpole Electronics Inc")
        (field (name "MANUFACTURER PART NUMBER") "RMCF0402FT10K0")
        (field (name "RESISTANCE IN OHMS") "10.0K")
        (field (name "POWER (WATTS)") "1/16W")
        (field (name "CASE") "0402")
        (field (name "TOLERANCE") "±1%")
      )
      (libsource (lib "Main Library") (part "R_0402_10.0K"))
    )
    (comp (ref "R228")
      (value "R_0402_10.0K")
      (footprint "R_0402")
      (description "RES 10.0K OHM 1/16W 1% 0402 SMD")
      (fields
        (field (name "MANUFACTURER") "Stackpole Electronics Inc")
        (field (name "MANUFACTURER PART NUMBER") "RMCF0402FT10K0")
        (field (name "RESISTANCE IN OHMS") "10.0K")
        (field (name "POWER (WATTS)") "1/16W")
        (field (name "CASE") "0402")
        (field (name "TOLERANCE") "±1%")
      )
      (libsource (lib "Main Library") (part "R_0402_10.0K"))
    )
    (comp (ref "R229")
      (value "R_0402_10.0K")
      (footprint "R_0402")
      (description "RES 10.0K OHM 1/16W 1% 0402 SMD")
      (fields
        (field (name "MANUFACTURER") "Stackpole Electronics Inc")
        (field (name "MANUFACTURER PART NUMBER") "RMCF0402FT10K0")
        (field (name "RESISTANCE IN OHMS") "10.0K")
        (field (name "POWER (WATTS)") "1/16W")
        (field (name "CASE") "0402")
        (field (name "TOLERANCE") "±1%")
      )
      (libsource (lib "Main Library") (part "R_0402_10.0K"))
    )
    (comp (ref "R230")
      (value "R_0402_10.0K")
      (footprint "R_0402")
      (description "RES 10.0K OHM 1/16W 1% 0402 SMD")
      (fields
        (field (name "MANUFACTURER") "Stackpole Electronics Inc")
        (field (name "MANUFACTURER PART NUMBER") "RMCF0402FT10K0")
        (field (name "RESISTANCE IN OHMS") "10.0K")
        (field (name "POWER (WATTS)") "1/16W")
        (field (name "CASE") "0402")
        (field (name "TOLERANCE") "±1%")
      )
      (libsource (lib "Main Library") (part "R_0402_10.0K"))
    )
    (comp (ref "R231")
      (value "R_0402_10.0K")
      (footprint "R_0402")
      (description "RES 10.0K OHM 1/16W 1% 0402 SMD")
      (fields
        (field (name "MANUFACTURER") "Stackpole Electronics Inc")
        (field (name "MANUFACTURER PART NUMBER") "RMCF0402FT10K0")
        (field (name "RESISTANCE IN OHMS") "10.0K")
        (field (name "POWER (WATTS)") "1/16W")
        (field (name "CASE") "0402")
        (field (name "TOLERANCE") "±1%")
      )
      (libsource (lib "Main Library") (part "R_0402_10.0K"))
    )
    (comp (ref "R232")
      (value "R_0402_10.0K")
      (footprint "R_0402")
      (description "RES 10.0K OHM 1/16W 1% 0402 SMD")
      (fields
        (field (name "MANUFACTURER") "Stackpole Electronics Inc")
        (field (name "MANUFACTURER PART NUMBER") "RMCF0402FT10K0")
        (field (name "RESISTANCE IN OHMS") "10.0K")
        (field (name "POWER (WATTS)") "1/16W")
        (field (name "CASE") "0402")
        (field (name "TOLERANCE") "±1%")
      )
      (libsource (lib "Main Library") (part "R_0402_10.0K"))
    )
    (comp (ref "R233")
      (value "R_0402_10.0K")
      (footprint "R_0402")
      (description "RES 10.0K OHM 1/16W 1% 0402 SMD")
      (fields
        (field (name "MANUFACTURER") "Stackpole Electronics Inc")
        (field (name "MANUFACTURER PART NUMBER") "RMCF0402FT10K0")
        (field (name "RESISTANCE IN OHMS") "10.0K")
        (field (name "POWER (WATTS)") "1/16W")
        (field (name "CASE") "0402")
        (field (name "TOLERANCE") "±1%")
      )
      (libsource (lib "Main Library") (part "R_0402_10.0K"))
    )
    (comp (ref "R234")
      (value "R_0402_10.0K")
      (footprint "R_0402")
      (description "RES 10.0K OHM 1/16W 1% 0402 SMD")
      (fields
        (field (name "MANUFACTURER") "Stackpole Electronics Inc")
        (field (name "MANUFACTURER PART NUMBER") "RMCF0402FT10K0")
        (field (name "RESISTANCE IN OHMS") "10.0K")
        (field (name "POWER (WATTS)") "1/16W")
        (field (name "CASE") "0402")
        (field (name "TOLERANCE") "±1%")
      )
      (libsource (lib "Main Library") (part "R_0402_10.0K"))
    )
    (comp (ref "R235")
      (value "R_0402_10.0K")
      (footprint "R_0402")
      (description "RES 10.0K OHM 1/16W 1% 0402 SMD")
      (fields
        (field (name "MANUFACTURER") "Stackpole Electronics Inc")
        (field (name "MANUFACTURER PART NUMBER") "RMCF0402FT10K0")
        (field (name "RESISTANCE IN OHMS") "10.0K")
        (field (name "POWER (WATTS)") "1/16W")
        (field (name "CASE") "0402")
        (field (name "TOLERANCE") "±1%")
      )
      (libsource (lib "Main Library") (part "R_0402_10.0K"))
    )
    (comp (ref "R236")
      (value "R_0402_10.0K")
      (footprint "R_0402")
      (description "RES 10.0K OHM 1/16W 1% 0402 SMD")
      (fields
        (field (name "MANUFACTURER") "Stackpole Electronics Inc")
        (field (name "MANUFACTURER PART NUMBER") "RMCF0402FT10K0")
        (field (name "RESISTANCE IN OHMS") "10.0K")
        (field (name "POWER (WATTS)") "1/16W")
        (field (name "CASE") "0402")
        (field (name "TOLERANCE") "±1%")
      )
      (libsource (lib "Main Library") (part "R_0402_10.0K"))
    )
    (comp (ref "R237")
      (value "R_0402_10.0K")
      (footprint "R_0402")
      (description "RES 10.0K OHM 1/16W 1% 0402 SMD")
      (fields
        (field (name "MANUFACTURER") "Stackpole Electronics Inc")
        (field (name "MANUFACTURER PART NUMBER") "RMCF0402FT10K0")
        (field (name "RESISTANCE IN OHMS") "10.0K")
        (field (name "POWER (WATTS)") "1/16W")
        (field (name "CASE") "0402")
        (field (name "TOLERANCE") "±1%")
      )
      (libsource (lib "Main Library") (part "R_0402_10.0K"))
    )
    (comp (ref "R238")
      (value "R_0402_10.0K")
      (footprint "R_0402")
      (description "RES 10.0K OHM 1/16W 1% 0402 SMD")
      (fields
        (field (name "MANUFACTURER") "Stackpole Electronics Inc")
        (field (name "MANUFACTURER PART NUMBER") "RMCF0402FT10K0")
        (field (name "RESISTANCE IN OHMS") "10.0K")
        (field (name "POWER (WATTS)") "1/16W")
        (field (name "CASE") "0402")
        (field (name "TOLERANCE") "±1%")
      )
      (libsource (lib "Main Library") (part "R_0402_10.0K"))
    )
    (comp (ref "R239")
      (value "R_0402_10.0K")
      (footprint "R_0402")
      (description "RES 10.0K OHM 1/16W 1% 0402 SMD")
      (fields
        (field (name "MANUFACTURER") "Stackpole Electronics Inc")
        (field (name "MANUFACTURER PART NUMBER") "RMCF0402FT10K0")
        (field (name "RESISTANCE IN OHMS") "10.0K")
        (field (name "POWER (WATTS)") "1/16W")
        (field (name "CASE") "0402")
        (field (name "TOLERANCE") "±1%")
      )
      (libsource (lib "Main Library") (part "R_0402_10.0K"))
    )
    (comp (ref "R240")
      (value "R_0402_10.0K")
      (footprint "R_0402")
      (description "RES 10.0K OHM 1/16W 1% 0402 SMD")
      (fields
        (field (name "MANUFACTURER") "Stackpole Electronics Inc")
        (field (name "MANUFACTURER PART NUMBER") "RMCF0402FT10K0")
        (field (name "RESISTANCE IN OHMS") "10.0K")
        (field (name "POWER (WATTS)") "1/16W")
        (field (name "CASE") "0402")
        (field (name "TOLERANCE") "±1%")
      )
      (libsource (lib "Main Library") (part "R_0402_10.0K"))
    )
    (comp (ref "R241")
      (value "R_0402_10.0K")
      (footprint "R_0402")
      (description "RES 10.0K OHM 1/16W 1% 0402 SMD")
      (fields
        (field (name "MANUFACTURER") "Stackpole Electronics Inc")
        (field (name "MANUFACTURER PART NUMBER") "RMCF0402FT10K0")
        (field (name "RESISTANCE IN OHMS") "10.0K")
        (field (name "POWER (WATTS)") "1/16W")
        (field (name "CASE") "0402")
        (field (name "TOLERANCE") "±1%")
      )
      (libsource (lib "Main Library") (part "R_0402_10.0K"))
    )
    (comp (ref "R242")
      (value "R_0402_10.0K")
      (footprint "R_0402")
      (description "RES 10.0K OHM 1/16W 1% 0402 SMD")
      (fields
        (field (name "MANUFACTURER") "Stackpole Electronics Inc")
        (field (name "MANUFACTURER PART NUMBER") "RMCF0402FT10K0")
        (field (name "RESISTANCE IN OHMS") "10.0K")
        (field (name "POWER (WATTS)") "1/16W")
        (field (name "CASE") "0402")
        (field (name "TOLERANCE") "±1%")
      )
      (libsource (lib "Main Library") (part "R_0402_10.0K"))
    )
    (comp (ref "R243")
      (value "R_0402_10.0K")
      (footprint "R_0402")
      (description "RES 10.0K OHM 1/16W 1% 0402 SMD")
      (fields
        (field (name "MANUFACTURER") "Stackpole Electronics Inc")
        (field (name "MANUFACTURER PART NUMBER") "RMCF0402FT10K0")
        (field (name "RESISTANCE IN OHMS") "10.0K")
        (field (name "POWER (WATTS)") "1/16W")
        (field (name "CASE") "0402")
        (field (name "TOLERANCE") "±1%")
      )
      (libsource (lib "Main Library") (part "R_0402_10.0K"))
    )
    (comp (ref "R244")
      (value "R_0402_10.0K")
      (footprint "R_0402")
      (description "RES 10.0K OHM 1/16W 1% 0402 SMD")
      (fields
        (field (name "MANUFACTURER") "Stackpole Electronics Inc")
        (field (name "MANUFACTURER PART NUMBER") "RMCF0402FT10K0")
        (field (name "RESISTANCE IN OHMS") "10.0K")
        (field (name "POWER (WATTS)") "1/16W")
        (field (name "CASE") "0402")
        (field (name "TOLERANCE") "±1%")
      )
      (libsource (lib "Main Library") (part "R_0402_10.0K"))
    )
    (comp (ref "R245")
      (value "R_0402_10.0K")
      (footprint "R_0402")
      (description "RES 10.0K OHM 1/16W 1% 0402 SMD")
      (fields
        (field (name "MANUFACTURER") "Stackpole Electronics Inc")
        (field (name "MANUFACTURER PART NUMBER") "RMCF0402FT10K0")
        (field (name "RESISTANCE IN OHMS") "10.0K")
        (field (name "POWER (WATTS)") "1/16W")
        (field (name "CASE") "0402")
        (field (name "TOLERANCE") "±1%")
      )
      (libsource (lib "Main Library") (part "R_0402_10.0K"))
    )
    (comp (ref "R246")
      (value "R_0402_10.0K")
      (footprint "R_0402")
      (description "RES 10.0K OHM 1/16W 1% 0402 SMD")
      (fields
        (field (name "MANUFACTURER") "Stackpole Electronics Inc")
        (field (name "MANUFACTURER PART NUMBER") "RMCF0402FT10K0")
        (field (name "RESISTANCE IN OHMS") "10.0K")
        (field (name "POWER (WATTS)") "1/16W")
        (field (name "CASE") "0402")
        (field (name "TOLERANCE") "±1%")
      )
      (libsource (lib "Main Library") (part "R_0402_10.0K"))
    )
    (comp (ref "U17")
      (value "U_TPS65105PWPR")
      (footprint "PWP0024B_L")
      (description "IC LCD SUPPLY TFT QUAD 24HTSSOP")
      (fields
        (field (name "VOLTAGE - OUTPUT") "Multiple")
        (field (name "MANUFACTURER") "Texas Instruments")
        (field (name "MANUFACTURER PART NUMBER") "TPS65105PWPR")
        (field (name "VOLTAGE - INPUT") "2.7 V ~ 5.8 V")
        (field (name "SUPPLIER DEVICE PACKAGE") "24-HTSSOP")
      )
      (libsource (lib "Cospan Design") (part "U_TPS65105PWPR"))
    )
    (comp (ref "U18")
      (value "U_LM3410XMFE")
      (footprint "MF05A_N")
      (description "IC DRVR WT/OLED BCKLT SOT23-5")
      (fields
        (field (name "MANUFACTURER") "Texas Instruments")
        (field (name "MANUFACTURER PART NUMBER") "LM3410XMFE/NOPB")
        (field (name "VOLTAGE - SUPPLY") "2.7 V ~ 5.5 V")
        (field (name "SUPPLIER DEVICE PACKAGE") "SOT-23-5")
      )
      (libsource (lib "Main Library") (part "U_LM3410XMFE"))
    )
  )
  (nets
    (net (code "4") (name "/LCD_BL_DIM") (class "Default")
      (node (ref "R167") (pin "2") (pinfunction "2_2") (pintype "passive"))
      (node (ref "U18") (pin "4") (pinfunction "DIM_4") (pintype "input"))
    )
    (net (code "5") (name "/LCD_CLK_N") (class "Default")
      (node (ref "C198") (pin "2") (pinfunction "2_2") (pintype "passive"))
    )
    (net (code "6") (name "/LCD_CLK_P") (class "Default")
      (node (ref "C197") (pin "2") (pinfunction "2_2") (pintype "passive"))
    )
    (net (code "7") (name "/LCD_PWR_EN") (class "Default")
      (node (ref "R153") (pin "2") (pinfunction "2_2") (pintype "passive"))
      (node (ref "U17") (pin "24") (pinfunction "EN_24") (pintype "input"))
    )
    (net (code "8") (name "/LCD_TX0_N") (class "Default")
      (node (ref "C200") (pin "2") (pinfunction "2_2") (pintype "passive"))
    )
    (net (code "9") (name "/LCD_TX0_P") (class "Default")
      (node (ref "C199") (pin "2") (pinfunction "2_2") (pintype "passive"))
    )
    (net (code "10") (name "/LCD_TX1_N") (class "Default")
      (node (ref "C202") (pin "2") (pinfunction "2_2") (pintype "passive"))
    )
    (net (code "11") (name "/LCD_TX1_P") (class "Default")
      (node (ref "C201") (pin "2") (pinfunction "2_2") (pintype "passive"))
    )
    (net (code "12") (name "/LCD_TX2_N") (class "Default")
      (node (ref "C204") (pin "2") (pinfunction "2_2") (pintype "passive"))
    )
    (net (code "13") (name "/LCD_TX2_P") (class "Default")
      (node (ref "C203") (pin "2") (pinfunction "2_2") (pintype "passive"))
    )
    (net (code "14") (name "/LCD_TX3_N") (class "Default")
      (node (ref "C206") (pin "2") (pinfunction "2_2") (pintype "passive"))
    )
    (net (code "15") (name "/LCD_TX3_P") (class "Default")
      (node (ref "C205") (pin "2") (pinfunction "2_2") (pintype "passive"))
    )
    (net (code "16") (name "/LCD_X_CLK_N") (class "Default")
      (node (ref "C203") (pin "1") (pinfunction "1_1") (pintype "passive"))
      (node (ref "J16") (pin "17") (pinfunction "RXCLK_IN_N_17") (pintype "passive"))
      (node (ref "R233") (pin "2") (pinfunction "2_2") (pintype "passive"))
      (node (ref "R243") (pin "1") (pinfunction "1_1") (pintype "passive"))
    )
    (net (code "17") (name "/LCD_X_CLK_P") (class "Default")
      (node (ref "C204") (pin "1") (pinfunction "1_1") (pintype "passive"))
      (node (ref "J16") (pin "18") (pinfunction "RXCLK_IN_P_18") (pintype "passive"))
      (node (ref "R234") (pin "2") (pinfunction "2_2") (pintype "passive"))
      (node (ref "R244") (pin "1") (pinfunction "1_1") (pintype "passive"))
    )
    (net (code "18") (name "/LCD_X_TX0_N") (class "Default")
      (node (ref "C197") (pin "1") (pinfunction "1_1") (pintype "passive"))
      (node (ref "J16") (pin "8") (pinfunction "TXIN0_N_8") (pintype "passive"))
      (node (ref "R227") (pin "2") (pinfunction "2_2") (pintype "passive"))
      (node (ref "R237") (pin "1") (pinfunction "1_1") (pintype "passive"))
    )
    (net (code "19") (name "/LCD_X_TX0_P") (class "Default")
      (node (ref "C198") (pin "1") (pinfunction "1_1") (pintype "passive"))
      (node (ref "J16") (pin "9") (pinfunction "TXIN0_P_9") (pintype "passive"))
      (node (ref "R228") (pin "2") (pinfunction "2_2") (pintype "passive"))
      (node (ref "R238") (pin "1") (pinfunction "1_1") (pintype "passive"))
    )
    (net (code "20") (name "/LCD_X_TX1_N") (class "Default")
      (node (ref "C199") (pin "1") (pinfunction "1_1") (pintype "passive"))
      (node (ref "J16") (pin "11") (pinfunction "RXIN1_N_11") (pintype "passive"))
      (node (ref "R229") (pin "2") (pinfunction "2_2") (pintype "passive"))
      (node (ref "R239") (pin "1") (pinfunction "1_1") (pintype "passive"))
    )
    (net (code "21") (name "/LCD_X_TX1_P") (class "Default")
      (node (ref "C200") (pin "1") (pinfunction "1_1") (pintype "passive"))
      (node (ref "J16") (pin "12") (pinfunction "RXIN1_P_12") (pintype "passive"))
      (node (ref "R230") (pin "2") (pinfunction "2_2") (pintype "passive"))
      (node (ref "R240") (pin "1") (pinfunction "1_1") (pintype "passive"))
    )
    (net (code "22") (name "/LCD_X_TX2_N") (class "Default")
      (node (ref "C201") (pin "1") (pinfunction "1_1") (pintype "passive"))
      (node (ref "J16") (pin "14") (pinfunction "RXIN2_N_14") (pintype "passive"))
      (node (ref "R231") (pin "2") (pinfunction "2_2") (pintype "passive"))
      (node (ref "R241") (pin "1") (pinfunction "1_1") (pintype "passive"))
    )
    (net (code "23") (name "/LCD_X_TX2_P") (class "Default")
      (node (ref "C202") (pin "1") (pinfunction "1_1") (pintype "passive"))
      (node (ref "J16") (pin "15") (pinfunction "RXIN2_P_15") (pintype "passive"))
      (node (ref "R232") (pin "2") (pinfunction "2_2") (pintype "passive"))
      (node (ref "R242") (pin "1") (pinfunction "1_1") (pintype "passive"))
    )
    (net (code "24") (name "/LCD_X_TX3_N") (class "Default")
      (node (ref "C205") (pin "1") (pinfunction "1_1") (pintype "passive"))
      (node (ref "J16") (pin "20") (pinfunction "RXIN3_N_20") (pintype "passive"))
      (node (ref "R235") (pin "2") (pinfunction "2_2") (pintype "passive"))
      (node (ref "R245") (pin "1") (pinfunction "1_1") (pintype "passive"))
    )
    (net (code "25") (name "/LCD_X_TX3_P") (class "Default")
      (node (ref "C206") (pin "1") (pinfunction "1_1") (pintype "passive"))
      (node (ref "J16") (pin "21") (pinfunction "RXIN3_P_21") (pintype "passive"))
      (node (ref "R236") (pin "2") (pinfunction "2_2") (pintype "passive"))
      (node (ref "R246") (pin "1") (pinfunction "1_1") (pintype "passive"))
    )
    (net (code "26") (name "/TFT_LED_N") (class "Default")
      (node (ref "J16") (pin "31") (pinfunction "LED_N_31") (pintype "passive"))
      (node (ref "J16") (pin "32") (pinfunction "LED_N_32") (pintype "passive"))
      (node (ref "R168") (pin "1") (pinfunction "1_1") (pintype "passive"))
      (node (ref "U18") (pin "3") (pinfunction "FB_3") (pintype "input"))
    )
    (net (code "27") (name "/TFT_LED_P") (class "Default")
      (node (ref "C132") (pin "2") (pinfunction "2_2") (pintype "passive"))
      (node (ref "D8") (pin "2") (pinfunction "K_2") (pintype "passive"))
      (node (ref "J16") (pin "39") (pinfunction "LED_P_39") (pintype "passive"))
      (node (ref "J16") (pin "40") (pinfunction "LED_P_40") (pintype "passive"))
    )
    (net (code "28") (name "/TFT_LR") (class "Default")
      (node (ref "J16") (pin "33") (pinfunction "L/R_33") (pintype "passive"))
      (node (ref "R162") (pin "1") (pinfunction "1_1") (pintype "passive"))
      (node (ref "R173") (pin "2") (pinfunction "2_2") (pintype "passive"))
    )
    (net (code "29") (name "/TFT_RESET") (class "Default")
      (node (ref "J16") (pin "5") (pinfunction "RESET_5") (pintype "passive"))
      (node (ref "Q11") (pin "1") (pinfunction "G_1") (pintype "passive"))
      (node (ref "R151") (pin "2") (pinfunction "2_2") (pintype "passive"))
    )
    (net (code "30") (name "/TFT_STBY_N") (class "Default")
      (node (ref "J16") (pin "6") (pinfunction "STBYB_6") (pintype "passive"))
      (node (ref "R154") (pin "2") (pinfunction "2_2") (pintype "passive"))
    )
    (net (code "31") (name "/TFT_UD") (class "Default")
      (node (ref "J16") (pin "34") (pinfunction "U/D_34") (pintype "passive"))
      (node (ref "R163") (pin "2") (pinfunction "2_2") (pintype "passive"))
      (node (ref "R172") (pin "2") (pinfunction "2_2") (pintype "passive"))
    )
    (net (code "32") (name "/TOUCH_INT_N") (class "Default")
      (node (ref "J11") (pin "5") (pinfunction "INT_5") (pintype "passive"))
    )
    (net (code "33") (name "/TOUCH_RST_N") (class "Default")
      (node (ref "J11") (pin "4") (pinfunction "RESET_4") (pintype "passive"))
      (node (ref "Q11") (pin "3") (pinfunction "D_3") (pintype "passive"))
      (node (ref "R175") (pin "1") (pinfunction "1_1") (pintype "passive"))
    )
    (net (code "34") (name "/TOUCH_SCL") (class "Default")
      (node (ref "J11") (pin "3") (pinfunction "SCL_3") (pintype "passive"))
    )
    (net (code "35") (name "/TOUCH_SDA") (class "Default")
      (node (ref "J11") (pin "2") (pinfunction "SDA_2") (pintype "passive"))
    )
    (net (code "38") (name "GND") (class "Default")
      (node (ref "C118") (pin "1") (pinfunction "1_1") (pintype "passive"))
      (node (ref "C119") (pin "1") (pinfunction "1_1") (pintype "passive"))
      (node (ref "C120") (pin "1") (pinfunction "1_1") (pintype "passive"))
      (node (ref "C121") (pin "1") (pinfunction "1_1") (pintype "passive"))
      (node (ref "C122") (pin "1") (pinfunction "1_1") (pintype "passive"))
      (node (ref "C124") (pin "2") (pinfunction "2_2") (pintype "passive"))
      (node (ref "C128") (pin "1") (pinfunction "1_1") (pintype "passive"))
      (node (ref "C129") (pin "1") (pinfunction "1_1") (pintype "passive"))
      (node (ref "C130") (pin "1") (pinfunction "1_1") (pintype "passive"))
      (node (ref "C131") (pin "1") (pinfunction "1_1") (pintype "passive"))
      (node (ref "C132") (pin "1") (pinfunction "1_1") (pintype "passive"))
      (node (ref "C133") (pin "1") (pinfunction "1_1") (pintype "passive"))
      (node (ref "C134") (pin "1") (pinfunction "1_1") (pintype "passive"))
      (node (ref "C135") (pin "1") (pinfunction "1_1") (pintype "passive"))
      (node (ref "C207") (pin "2") (pinfunction "2_2") (pintype "passive"))
      (node (ref "D7") (pin "1") (pinfunction "1_1") (pintype "passive"))
      (node (ref "J11") (pin "1") (pinfunction "GND_1") (pintype "passive"))
      (node (ref "J11") (pin "10") (pinfunction "GND_10") (pintype "passive"))
      (node (ref "J11") (pin "9") (pinfunction "GND_9") (pintype "passive"))
      (node (ref "J16") (pin "10") (pinfunction "GND_10") (pintype "passive"))
      (node (ref "J16") (pin "13") (pinfunction "GND_13") (pintype "passive"))
      (node (ref "J16") (pin "16") (pinfunction "GND_16") (pintype "passive"))
      (node (ref "J16") (pin "19") (pinfunction "GND_19") (pintype "passive"))
      (node (ref "J16") (pin "22") (pinfunction "GND_22") (pintype "passive"))
      (node (ref "J16") (pin "25") (pinfunction "GND_25") (pintype "passive"))
      (node (ref "J16") (pin "30") (pinfunction "GND_30") (pintype "passive"))
      (node (ref "J16") (pin "7") (pinfunction "GND_7") (pintype "passive"))
      (node (ref "Q11") (pin "2") (pinfunction "S_2") (pintype "passive"))
      (node (ref "R151") (pin "1") (pinfunction "1_1") (pintype "passive"))
      (node (ref "R152") (pin "2") (pinfunction "2_2") (pintype "passive"))
      (node (ref "R153") (pin "1") (pinfunction "1_1") (pintype "passive"))
      (node (ref "R156") (pin "2") (pinfunction "2_2") (pintype "passive"))
      (node (ref "R159") (pin "2") (pinfunction "2_2") (pintype "passive"))
      (node (ref "R167") (pin "1") (pinfunction "1_1") (pintype "passive"))
      (node (ref "R168") (pin "2") (pinfunction "2_2") (pintype "passive"))
      (node (ref "R169") (pin "2") (pinfunction "2_2") (pintype "passive"))
      (node (ref "R170") (pin "1") (pinfunction "1_1") (pintype "passive"))
      (node (ref "R171") (pin "1") (pinfunction "1_1") (pintype "passive"))
      (node (ref "R172") (pin "1") (pinfunction "1_1") (pintype "passive"))
      (node (ref "R173") (pin "1") (pinfunction "1_1") (pintype "passive"))
      (node (ref "R174") (pin "1") (pinfunction "1_1") (pintype "passive"))
      (node (ref "R237") (pin "2") (pinfunction "2_2") (pintype "passive"))
      (node (ref "R238") (pin "2") (pinfunction "2_2") (pintype "passive"))
      (node (ref "R239") (pin "2") (pinfunction "2_2") (pintype "passive"))
      (node (ref "R240") (pin "2") (pinfunction "2_2") (pintype "passive"))
      (node (ref "R241") (pin "2") (pinfunction "2_2") (pintype "passive"))
      (node (ref "R242") (pin "2") (pinfunction "2_2") (pintype "passive"))
      (node (ref "R243") (pin "2") (pinfunction "2_2") (pintype "passive"))
      (node (ref "R244") (pin "2") (pinfunction "2_2") (pintype "passive"))
      (node (ref "R245") (pin "2") (pinfunction "2_2") (pintype "passive"))
      (node (ref "R246") (pin "2") (pinfunction "2_2") (pintype "passive"))
      (node (ref "U17") (pin "19") (pinfunction "GND_19") (pintype "power_in"))
      (node (ref "U17") (pin "23") (pinfunction "ENR_23") (pintype "input"))
      (node (ref "U17") (pin "25") (pinfunction "EP_25") (pintype "power_in"))
      (node (ref "U17") (pin "7") (pinfunction "PGND_7") (pintype "power_in"))
      (node (ref "U17") (pin "8") (pinfunction "PGND_8") (pintype "power_in"))
      (node (ref "U18") (pin "2") (pinfunction "GND_2") (pintype "power_in"))
    )
    (net (code "39") (name "Net-(C126-Pad1)") (class "Default")
      (node (ref "C126") (pin "1") (pinfunction "1_1") (pintype "passive"))
      (node (ref "R159") (pin "1") (pinfunction "1_1") (pintype "passive"))
    )
    (net (code "40") (name "Net-(C127-Pad1)") (class "Default")
      (node (ref "C127") (pin "1") (pinfunction "1_1") (pintype "passive"))
      (node (ref "D6") (pin "1") (pinfunction "1_1") (pintype "passive"))
      (node (ref "D7") (pin "2") (pinfunction "2_2") (pintype "passive"))
    )
    (net (code "41") (name "Net-(D5-Pad2)") (class "Default")
      (node (ref "D5") (pin "2") (pinfunction "2_2") (pintype "passive"))
      (node (ref "L7") (pin "2") (pintype "passive"))
    )
    (net (code "42") (name "Net-(D8-A)") (class "Default")
      (node (ref "D8") (pin "1") (pinfunction "A_1") (pintype "passive"))
      (node (ref "L8") (pin "2") (pintype "passive"))
      (node (ref "U18") (pin "1") (pinfunction "SW_1") (pintype "power_in"))
    )
    (net (code "43") (name "Net-(J16-CABCEN0)") (class "Default")
      (node (ref "J16") (pin "37") (pinfunction "CABCEN0_37") (pintype "passive"))
      (node (ref "R166") (pin "2") (pinfunction "2_2") (pintype "passive"))
      (node (ref "R170") (pin "2") (pinfunction "2_2") (pintype "passive"))
    )
    (net (code "44") (name "Net-(J16-CABCEN1)") (class "Default")
      (node (ref "J16") (pin "36") (pinfunction "CABCEN1_36") (pintype "passive"))
      (node (ref "R165") (pin "2") (pinfunction "2_2") (pintype "passive"))
      (node (ref "R171") (pin "2") (pinfunction "2_2") (pintype "passive"))
    )
    (net (code "45") (name "Net-(J16-DIMO)") (class "Default")
      (node (ref "J16") (pin "27") (pinfunction "DIMO_27") (pintype "passive"))
      (node (ref "R157") (pin "2") (pinfunction "2_2") (pintype "passive"))
    )
    (net (code "46") (name "Net-(J16-SELB)") (class "Default")
      (node (ref "J16") (pin "28") (pinfunction "SELB_28") (pintype "passive"))
      (node (ref "R158") (pin "1") (pinfunction "1_1") (pintype "passive"))
      (node (ref "R174") (pin "2") (pinfunction "2_2") (pintype "passive"))
    )
    (net (code "47") (name "Net-(U17-C1+)") (class "Default")
      (node (ref "C123") (pin "1") (pinfunction "1_1") (pintype "passive"))
      (node (ref "U17") (pin "16") (pinfunction "C1+_16") (pintype "passive"))
    )
    (net (code "48") (name "Net-(U17-C1-)") (class "Default")
      (node (ref "C123") (pin "2") (pinfunction "2_2") (pintype "passive"))
      (node (ref "U17") (pin "17") (pinfunction "C1-_17") (pintype "passive"))
    )
    (net (code "49") (name "Net-(U17-C2+)") (class "Default")
      (node (ref "C125") (pin "1") (pinfunction "1_1") (pintype "passive"))
      (node (ref "U17") (pin "14") (pinfunction "C2+_14") (pintype "passive"))
    )
    (net (code "50") (name "Net-(U17-C2-{slash}MODE)") (class "Default")
      (node (ref "C125") (pin "2") (pinfunction "2_2") (pintype "passive"))
      (node (ref "U17") (pin "15") (pinfunction "C2-/MODE_15") (pintype "passive"))
    )
    (net (code "51") (name "Net-(U17-COMP)") (class "Default")
      (node (ref "C126") (pin "2") (pinfunction "2_2") (pintype "passive"))
      (node (ref "U17") (pin "22") (pinfunction "COMP_22") (pintype "passive"))
    )
    (net (code "52") (name "Net-(U17-DRV)") (class "Default")
      (node (ref "C127") (pin "2") (pinfunction "2_2") (pintype "passive"))
      (node (ref "U17") (pin "18") (pinfunction "DRV_18") (pintype "power_in"))
    )
    (net (code "53") (name "Net-(U17-FB1)") (class "Default")
      (node (ref "C117") (pin "1") (pinfunction "1_1") (pintype "passive"))
      (node (ref "R150") (pin "2") (pinfunction "2_2") (pintype "passive"))
      (node (ref "R152") (pin "1") (pinfunction "1_1") (pintype "passive"))
      (node (ref "U17") (pin "1") (pinfunction "FB1_1") (pintype "input"))
    )
    (net (code "54") (name "Net-(U17-FB2)") (class "Default")
      (node (ref "C129") (pin "2") (pinfunction "2_2") (pintype "passive"))
      (node (ref "R160") (pin "2") (pinfunction "2_2") (pintype "passive"))
      (node (ref "R164") (pin "1") (pinfunction "1_1") (pintype "passive"))
      (node (ref "U17") (pin "21") (pinfunction "FB2_21") (pintype "input"))
    )
    (net (code "55") (name "Net-(U17-FB3)") (class "Default")
      (node (ref "R155") (pin "2") (pinfunction "2_2") (pintype "passive"))
      (node (ref "R156") (pin "1") (pinfunction "1_1") (pintype "passive"))
      (node (ref "U17") (pin "12") (pinfunction "FB3_12") (pintype "input"))
    )
    (net (code "56") (name "Net-(U17-REF)") (class "Default")
      (node (ref "R164") (pin "2") (pinfunction "2_2") (pintype "passive"))
      (node (ref "U17") (pin "20") (pinfunction "REF_20") (pintype "output"))
    )
    (net (code "57") (name "Net-(U17-VCOMIN)") (class "Default")
      (node (ref "C134") (pin "2") (pinfunction "2_2") (pintype "passive"))
      (node (ref "R161") (pin "2") (pinfunction "2_2") (pintype "passive"))
      (node (ref "R169") (pin "1") (pinfunction "1_1") (pintype "passive"))
      (node (ref "U17") (pin "11") (pinfunction "VCOMIN_11") (pintype "input"))
    )
    (net (code "58") (name "TFT_AVDD") (class "Default")
      (node (ref "C117") (pin "2") (pinfunction "2_2") (pintype "passive"))
      (node (ref "C118") (pin "2") (pinfunction "2_2") (pintype "passive"))
      (node (ref "C119") (pin "2") (pinfunction "2_2") (pintype "passive"))
      (node (ref "D5") (pin "1") (pinfunction "1_1") (pintype "passive"))
      (node (ref "J16") (pin "29") (pinfunction "AVDD_29") (pintype "passive"))
      (node (ref "R150") (pin "1") (pinfunction "1_1") (pintype "passive"))
      (node (ref "R161") (pin "1") (pinfunction "1_1") (pintype "passive"))
      (node (ref "U17") (pin "5") (pinfunction "SW_5") (pintype "power_in"))
      (node (ref "U17") (pin "6") (pinfunction "SW_6") (pintype "power_in"))
      (node (ref "U17") (pin "9") (pinfunction "SUP_9") (pintype "power_in"))
    )
    (net (code "59") (name "TFT_VCOM") (class "Default")
      (node (ref "C133") (pin "2") (pinfunction "2_2") (pintype "passive"))
      (node (ref "J16") (pin "1") (pinfunction "VCOM_1") (pintype "passive"))
      (node (ref "U17") (pin "10") (pinfunction "VCOM_10") (pintype "power_in"))
    )
    (net (code "60") (name "TFT_VGH") (class "Default")
      (node (ref "C124") (pin "1") (pinfunction "1_1") (pintype "passive"))
      (node (ref "J16") (pin "38") (pinfunction "VGH_38") (pintype "passive"))
      (node (ref "R155") (pin "1") (pinfunction "1_1") (pintype "passive"))
      (node (ref "U17") (pin "13") (pinfunction "OUT3_13") (pintype "power_in"))
    )
    (net (code "61") (name "TFT_VGL") (class "Default")
      (node (ref "C128") (pin "2") (pinfunction "2_2") (pintype "passive"))
      (node (ref "C207") (pin "1") (pinfunction "1_1") (pintype "passive"))
      (node (ref "D6") (pin "2") (pinfunction "2_2") (pintype "passive"))
      (node (ref "J16") (pin "35") (pinfunction "VGL_35") (pintype "passive"))
      (node (ref "R160") (pin "1") (pinfunction "1_1") (pintype "passive"))
    )
    (net (code "62") (name "V2P5") (class "Default")
      (node (ref "R227") (pin "1") (pinfunction "1_1") (pintype "passive"))
      (node (ref "R228") (pin "1") (pinfunction "1_1") (pintype "passive"))
      (node (ref "R229") (pin "1") (pinfunction "1_1") (pintype "passive"))
      (node (ref "R230") (pin "1") (pinfunction "1_1") (pintype "passive"))
      (node (ref "R231") (pin "1") (pinfunction "1_1") (pintype "passive"))
      (node (ref "R232") (pin "1") (pinfunction "1_1") (pintype "passive"))
      (node (ref "R233") (pin "1") (pinfunction "1_1") (pintype "passive"))
      (node (ref "R234") (pin "1") (pinfunction "1_1") (pintype "passive"))
      (node (ref "R235") (pin "1") (pinfunction "1_1") (pintype "passive"))
      (node (ref "R236") (pin "1") (pinfunction "1_1") (pintype "passive"))
    )
    (net (code "63") (name "V3P3") (class "Default")
      (node (ref "C122") (pin "2") (pinfunction "2_2") (pintype "passive"))
      (node (ref "C130") (pin "2") (pinfunction "2_2") (pintype "passive"))
      (node (ref "C131") (pin "2") (pinfunction "2_2") (pintype "passive"))
      (node (ref "C135") (pin "2") (pinfunction "2_2") (pintype "passive"))
      (node (ref "J11") (pin "7") (pinfunction "VDD_7") (pintype "passive"))
      (node (ref "J11") (pin "8") (pinfunction "VDD_8") (pintype "passive"))
      (node (ref "J16") (pin "2") (pinfunction "VDD_2") (pintype "passive"))
      (node (ref "J16") (pin "3") (pinfunction "VDD_3") (pintype "passive"))
      (node (ref "L8") (pin "1") (pintype "passive"))
      (node (ref "R154") (pin "1") (pinfunction "1_1") (pintype "passive"))
      (node (ref "R158") (pin "2") (pinfunction "2_2") (pintype "passive"))
      (node (ref "R162") (pin "2") (pinfunction "2_2") (pintype "passive"))
      (node (ref "R163") (pin "1") (pinfunction "1_1") (pintype "passive"))
      (node (ref "R165") (pin "1") (pinfunction "1_1") (pintype "passive"))
      (node (ref "R166") (pin "1") (pinfunction "1_1") (pintype "passive"))
      (node (ref "R175") (pin "2") (pinfunction "2_2") (pintype "passive"))
      (node (ref "U18") (pin "5") (pinfunction "VIN_5") (pintype "power_in"))
    )
    (net (code "64") (name "V5P0") (class "Default")
      (node (ref "C120") (pin "2") (pinfunction "2_2") (pintype "passive"))
      (node (ref "C121") (pin "2") (pinfunction "2_2") (pintype "passive"))
      (node (ref "L7") (pin "1") (pintype "passive"))
      (node (ref "U17") (pin "2") (pinfunction "FB4_2") (pintype "input"))
      (node (ref "U17") (pin "3") (pinfunction "BASE_3") (pintype "output"))
      (node (ref "U17") (pin "4") (pinfunction "VIN_4") (pintype "power_in"))
    )
    (net (code "65") (name "unconnected-(J11-NC-Pad6)") (class "Default")
      (node (ref "J11") (pin "6") (pinfunction "NC_6") (pintype "passive+no_connect"))
    )
    (net (code "66") (name "unconnected-(J16-NC-Pad4)") (class "Default")
      (node (ref "J16") (pin "4") (pinfunction "NC_4") (pintype "passive+no_connect"))
    )
    (net (code "67") (name "unconnected-(J16-NC-Pad23)") (class "Default")
      (node (ref "J16") (pin "23") (pinfunction "NC_23") (pintype "passive+no_connect"))
    )
    (net (code "68") (name "unconnected-(J16-NC-Pad24)") (class "Default")
      (node (ref "J16") (pin "24") (pinfunction "NC_24") (pintype "passive+no_connect"))
    )
    (net (code "69") (name "unconnected-(J16-NC-Pad26)") (class "Default")
      (node (ref "J16") (pin "26") (pinfunction "NC_26") (pintype "passive+no_connect"))
    )
    (net (code "70") (name "unconnected-(R157-Pad1)") (class "Default")
      (node (ref "R157") (pin "1") (pinfunction "1_1") (pintype "passive+no_connect"))
    )
  )
)
